# ethernet_dip_v1.net
KiCad netlist of a schematic drawn in EAGLE
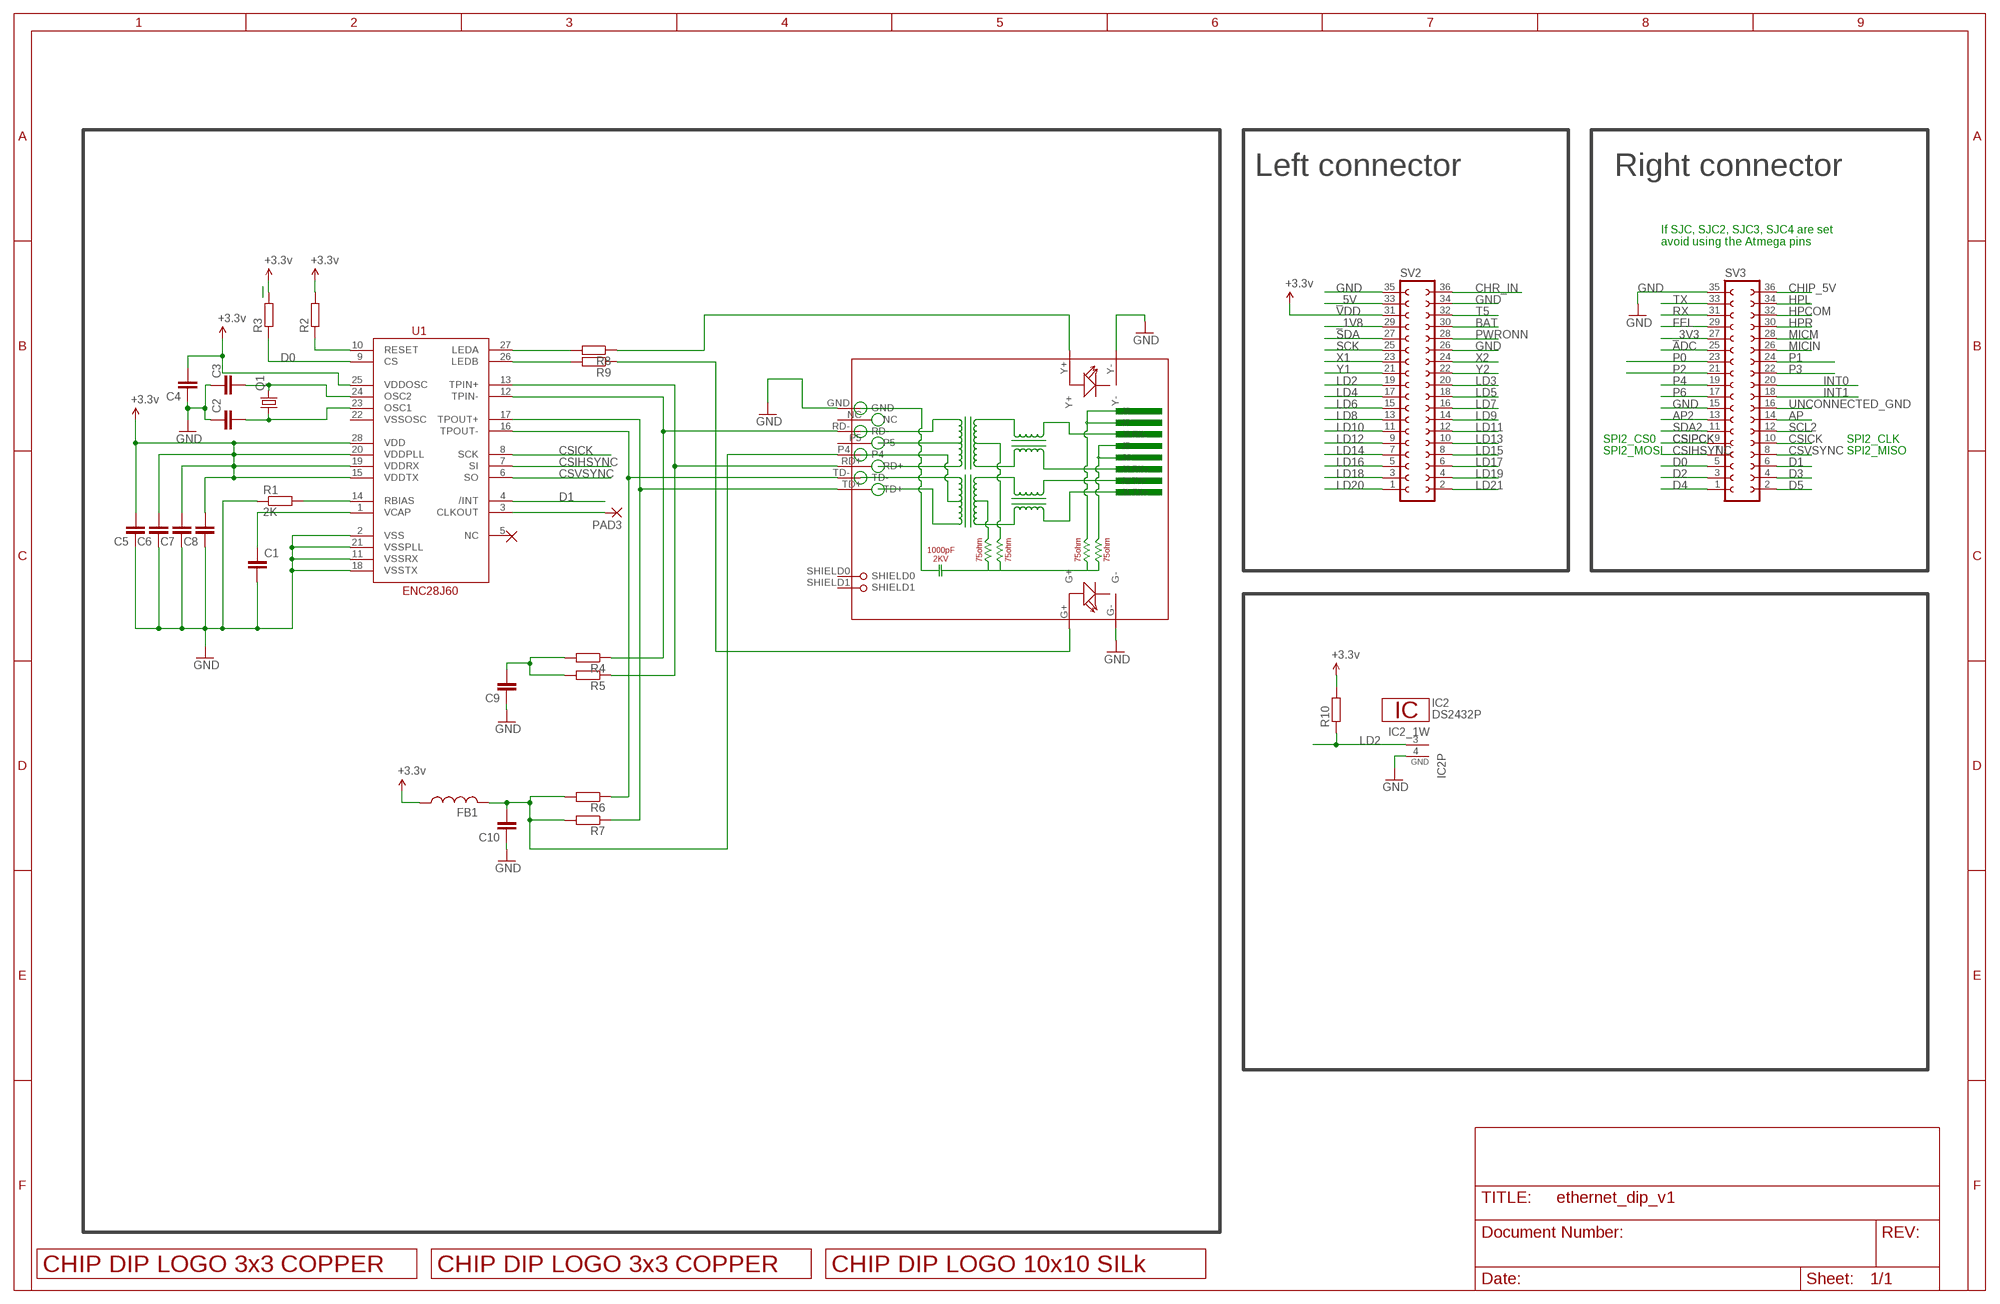
[diagram p0: schematic, sheet 1]

(export (version "E")
  (design (tool "Eeschema 10.0.6"))
  (components
    (comp (ref "C1")
      (value "C-EUC0805")
      (footprint "eagle-import:C0805")
      (libsource (lib "eagle-import") (part "C-EUC0805"))
    )
    (comp (ref "C2")
      (value "C-EUC0805")
      (footprint "eagle-import:C0805")
      (libsource (lib "eagle-import") (part "C-EUC0805"))
    )
    (comp (ref "C3")
      (value "C-EUC0805")
      (footprint "eagle-import:C0805")
      (libsource (lib "eagle-import") (part "C-EUC0805"))
    )
    (comp (ref "C4")
      (value "C-EUC0805")
      (footprint "eagle-import:C0805")
      (libsource (lib "eagle-import") (part "C-EUC0805"))
    )
    (comp (ref "C5")
      (value "C-EUC0805")
      (footprint "eagle-import:C0805")
      (libsource (lib "eagle-import") (part "C-EUC0805"))
    )
    (comp (ref "C6")
      (value "C-EUC0805")
      (footprint "eagle-import:C0805")
      (libsource (lib "eagle-import") (part "C-EUC0805"))
    )
    (comp (ref "C7")
      (value "C-EUC0805")
      (footprint "eagle-import:C0805")
      (libsource (lib "eagle-import") (part "C-EUC0805"))
    )
    (comp (ref "C8")
      (value "C-EUC0805")
      (footprint "eagle-import:C0805")
      (libsource (lib "eagle-import") (part "C-EUC0805"))
    )
    (comp (ref "C9")
      (value "C-EUC0805")
      (footprint "eagle-import:C0805")
      (libsource (lib "eagle-import") (part "C-EUC0805"))
    )
    (comp (ref "C10")
      (value "C-EUC0805")
      (footprint "eagle-import:C0805")
      (libsource (lib "eagle-import") (part "C-EUC0805"))
    )
    (comp (ref "FB1")
      (value "FERRITE-BEADB")
      (footprint "eagle-import:0805")
      (libsource (lib "eagle-import") (part "FERRITE-BEADB"))
    )
    (comp (ref "IC2")
      (value "DS2432P")
      (footprint "eagle-import:TSOC6")
      (libsource (lib "eagle-import") (part "DS2432P"))
    )
    (comp (ref "PAD3")
      (value "WIREPADSMD1,27-254")
      (footprint "eagle-import:SMD1,27-2,54")
      (libsource (lib "eagle-import") (part "WIREPADSMD1,27-254"))
    )
    (comp (ref "Q1")
      (value "CRYSTALSM49")
      (footprint "eagle-import:SM49")
      (libsource (lib "eagle-import") (part "CRYSTALSM49"))
    )
    (comp (ref "R1")
      (value "2K")
      (footprint "eagle-import:R0805")
      (libsource (lib "eagle-import") (part "R-EU_R0805"))
    )
    (comp (ref "R2")
      (value "R-EU_R0805")
      (footprint "eagle-import:R0805")
      (libsource (lib "eagle-import") (part "R-EU_R0805"))
    )
    (comp (ref "R3")
      (value "R-EU_R0805")
      (footprint "eagle-import:R0805")
      (libsource (lib "eagle-import") (part "R-EU_R0805"))
    )
    (comp (ref "R4")
      (value "R-EU_R0805")
      (footprint "eagle-import:R0805")
      (libsource (lib "eagle-import") (part "R-EU_R0805"))
    )
    (comp (ref "R5")
      (value "R-EU_R0805")
      (footprint "eagle-import:R0805")
      (libsource (lib "eagle-import") (part "R-EU_R0805"))
    )
    (comp (ref "R6")
      (value "R-EU_R0805")
      (footprint "eagle-import:R0805")
      (libsource (lib "eagle-import") (part "R-EU_R0805"))
    )
    (comp (ref "R7")
      (value "R-EU_R0805")
      (footprint "eagle-import:R0805")
      (libsource (lib "eagle-import") (part "R-EU_R0805"))
    )
    (comp (ref "R8")
      (value "R-EU_R0805")
      (footprint "eagle-import:R0805")
      (libsource (lib "eagle-import") (part "R-EU_R0805"))
    )
    (comp (ref "R9")
      (value "R-EU_R0805")
      (footprint "eagle-import:R0805")
      (libsource (lib "eagle-import") (part "R-EU_R0805"))
    )
    (comp (ref "R10")
      (value "R-EU_R0805")
      (footprint "eagle-import:R0805")
      (libsource (lib "eagle-import") (part "R-EU_R0805"))
    )
    (comp (ref "RJ1")
      (value "HR911105A")
      (footprint "eagle-import:HR911105A")
      (libsource (lib "eagle-import") (part "HR911105A"))
    )
    (comp (ref "SV2")
      (value "FE18-2")
      (footprint "eagle-import:FE18-2")
      (libsource (lib "eagle-import") (part "FE18-2"))
    )
    (comp (ref "SV3")
      (value "FE18-2")
      (footprint "eagle-import:FE18-2")
      (libsource (lib "eagle-import") (part "FE18-2"))
    )
    (comp (ref "U$2")
      (value "LOGO_3X3_COPPER")
      (footprint "eagle-import:LOGO_3X3_COPPER")
      (libsource (lib "eagle-import") (part "LOGO_3X3_COPPER"))
    )
    (comp (ref "U$4")
      (value "LOGO_3X3_COPPER")
      (footprint "eagle-import:LOGO_3X3_COPPER")
      (libsource (lib "eagle-import") (part "LOGO_3X3_COPPER"))
    )
    (comp (ref "U$5")
      (value "LOGO_10X10_SILK")
      (footprint "eagle-import:LOGO_10X10_SILK")
      (libsource (lib "eagle-import") (part "LOGO_10X10_SILK"))
    )
    (comp (ref "U1")
      (value "ENC28J60")
      (footprint "eagle-import:SSOP28DB")
      (libsource (lib "eagle-import") (part "ENC28J60"))
    )
  )
  (nets
    (net (code "1") (name "+3.3v") (class "Default")
      (node (ref "C4") (pin "2") (pinfunction "2_2") (pintype "passive"))
      (node (ref "C5") (pin "2") (pinfunction "2_2") (pintype "passive"))
      (node (ref "C6") (pin "2") (pinfunction "2_2") (pintype "passive"))
      (node (ref "C7") (pin "2") (pinfunction "2_2") (pintype "passive"))
      (node (ref "C8") (pin "2") (pinfunction "2_2") (pintype "passive"))
      (node (ref "FB1") (pin "1") (pinfunction "1_1") (pintype "passive"))
      (node (ref "R10") (pin "2") (pinfunction "2_2") (pintype "passive"))
      (node (ref "R2") (pin "2") (pinfunction "2_2") (pintype "passive"))
      (node (ref "R3") (pin "2") (pinfunction "2_2") (pintype "passive"))
      (node (ref "SV2") (pin "31") (pinfunction "31_31") (pintype "passive"))
      (node (ref "U1") (pin "15") (pinfunction "VDDTX_15") (pintype "bidirectional"))
      (node (ref "U1") (pin "19") (pinfunction "VDDRX_19") (pintype "bidirectional"))
      (node (ref "U1") (pin "20") (pinfunction "VDDPLL_20") (pintype "bidirectional"))
      (node (ref "U1") (pin "25") (pinfunction "VDDOSC_25") (pintype "bidirectional"))
      (node (ref "U1") (pin "28") (pinfunction "VDD_28") (pintype "bidirectional"))
    )
    (net (code "2") (name "/ADC") (class "Default")
      (node (ref "SV3") (pin "25") (pinfunction "25_25") (pintype "passive"))
    )
    (net (code "3") (name "/AP") (class "Default")
      (node (ref "SV3") (pin "14") (pinfunction "14_14") (pintype "passive"))
    )
    (net (code "4") (name "/AP2") (class "Default")
      (node (ref "SV3") (pin "13") (pinfunction "13_13") (pintype "passive"))
    )
    (net (code "5") (name "/BAT") (class "Default")
      (node (ref "SV2") (pin "30") (pinfunction "30_30") (pintype "passive"))
    )
    (net (code "6") (name "/CHIP_5V") (class "Default")
      (node (ref "SV3") (pin "36") (pinfunction "36_36") (pintype "passive"))
    )
    (net (code "7") (name "/CHR_IN") (class "Default")
      (node (ref "SV2") (pin "36") (pinfunction "36_36") (pintype "passive"))
    )
    (net (code "8") (name "/CSICK") (class "Default")
      (node (ref "SV3") (pin "10") (pinfunction "10_10") (pintype "passive"))
      (node (ref "U1") (pin "8") (pinfunction "SCK_8") (pintype "bidirectional"))
    )
    (net (code "9") (name "/CSIHSYNC") (class "Default")
      (node (ref "SV3") (pin "7") (pinfunction "7_7") (pintype "passive"))
      (node (ref "U1") (pin "7") (pinfunction "SI_7") (pintype "bidirectional"))
    )
    (net (code "10") (name "/CSIPCK") (class "Default")
      (node (ref "SV3") (pin "9") (pinfunction "9_9") (pintype "passive"))
    )
    (net (code "11") (name "/CSVSYNC") (class "Default")
      (node (ref "SV3") (pin "8") (pinfunction "8_8") (pintype "passive"))
      (node (ref "U1") (pin "6") (pinfunction "SO_6") (pintype "bidirectional"))
    )
    (net (code "12") (name "/D0") (class "Default")
      (node (ref "R3") (pin "1") (pinfunction "1_1") (pintype "passive"))
      (node (ref "SV3") (pin "5") (pinfunction "5_5") (pintype "passive"))
      (node (ref "U1") (pin "9") (pinfunction "CS_9") (pintype "bidirectional"))
    )
    (net (code "13") (name "/D1") (class "Default")
      (node (ref "SV3") (pin "6") (pinfunction "6_6") (pintype "passive"))
      (node (ref "U1") (pin "4") (pinfunction "/INT_4") (pintype "bidirectional"))
    )
    (net (code "14") (name "/D2") (class "Default")
      (node (ref "SV3") (pin "3") (pinfunction "3_3") (pintype "passive"))
    )
    (net (code "15") (name "/D3") (class "Default")
      (node (ref "SV3") (pin "4") (pinfunction "4_4") (pintype "passive"))
    )
    (net (code "16") (name "/D4") (class "Default")
      (node (ref "SV3") (pin "1") (pinfunction "1_1") (pintype "passive"))
    )
    (net (code "17") (name "/D5") (class "Default")
      (node (ref "SV3") (pin "2") (pinfunction "2_2") (pintype "passive"))
    )
    (net (code "18") (name "/FEL") (class "Default")
      (node (ref "SV3") (pin "29") (pinfunction "29_29") (pintype "passive"))
    )
    (net (code "19") (name "/HPCOM") (class "Default")
      (node (ref "SV3") (pin "32") (pinfunction "32_32") (pintype "passive"))
    )
    (net (code "20") (name "/HPL") (class "Default")
      (node (ref "SV3") (pin "34") (pinfunction "34_34") (pintype "passive"))
    )
    (net (code "21") (name "/HPR") (class "Default")
      (node (ref "SV3") (pin "30") (pinfunction "30_30") (pintype "passive"))
    )
    (net (code "22") (name "/INT0") (class "Default")
      (node (ref "SV3") (pin "20") (pinfunction "20_20") (pintype "passive"))
    )
    (net (code "23") (name "/INT1") (class "Default")
      (node (ref "SV3") (pin "18") (pinfunction "18_18") (pintype "passive"))
    )
    (net (code "24") (name "/LD2") (class "Default")
      (node (ref "IC2") (pin "3") (pinfunction "1W_3") (pintype "power_in"))
      (node (ref "R10") (pin "1") (pinfunction "1_1") (pintype "passive"))
      (node (ref "SV2") (pin "19") (pinfunction "19_19") (pintype "passive"))
    )
    (net (code "25") (name "/LD3") (class "Default")
      (node (ref "SV2") (pin "20") (pinfunction "20_20") (pintype "passive"))
    )
    (net (code "26") (name "/LD4") (class "Default")
      (node (ref "SV2") (pin "17") (pinfunction "17_17") (pintype "passive"))
    )
    (net (code "27") (name "/LD5") (class "Default")
      (node (ref "SV2") (pin "18") (pinfunction "18_18") (pintype "passive"))
    )
    (net (code "28") (name "/LD6") (class "Default")
      (node (ref "SV2") (pin "15") (pinfunction "15_15") (pintype "passive"))
    )
    (net (code "29") (name "/LD7") (class "Default")
      (node (ref "SV2") (pin "16") (pinfunction "16_16") (pintype "passive"))
    )
    (net (code "30") (name "/LD8") (class "Default")
      (node (ref "SV2") (pin "13") (pinfunction "13_13") (pintype "passive"))
    )
    (net (code "31") (name "/LD9") (class "Default")
      (node (ref "SV2") (pin "14") (pinfunction "14_14") (pintype "passive"))
    )
    (net (code "32") (name "/LD10") (class "Default")
      (node (ref "SV2") (pin "11") (pinfunction "11_11") (pintype "passive"))
    )
    (net (code "33") (name "/LD11") (class "Default")
      (node (ref "SV2") (pin "12") (pinfunction "12_12") (pintype "passive"))
    )
    (net (code "34") (name "/LD12") (class "Default")
      (node (ref "SV2") (pin "9") (pinfunction "9_9") (pintype "passive"))
    )
    (net (code "35") (name "/LD13") (class "Default")
      (node (ref "SV2") (pin "10") (pinfunction "10_10") (pintype "passive"))
    )
    (net (code "36") (name "/LD14") (class "Default")
      (node (ref "SV2") (pin "7") (pinfunction "7_7") (pintype "passive"))
    )
    (net (code "37") (name "/LD15") (class "Default")
      (node (ref "SV2") (pin "8") (pinfunction "8_8") (pintype "passive"))
    )
    (net (code "38") (name "/LD16") (class "Default")
      (node (ref "SV2") (pin "5") (pinfunction "5_5") (pintype "passive"))
    )
    (net (code "39") (name "/LD17") (class "Default")
      (node (ref "SV2") (pin "6") (pinfunction "6_6") (pintype "passive"))
    )
    (net (code "40") (name "/LD18") (class "Default")
      (node (ref "SV2") (pin "3") (pinfunction "3_3") (pintype "passive"))
    )
    (net (code "41") (name "/LD19") (class "Default")
      (node (ref "SV2") (pin "4") (pinfunction "4_4") (pintype "passive"))
    )
    (net (code "42") (name "/LD20") (class "Default")
      (node (ref "SV2") (pin "1") (pinfunction "1_1") (pintype "passive"))
    )
    (net (code "43") (name "/LD21") (class "Default")
      (node (ref "SV2") (pin "2") (pinfunction "2_2") (pintype "passive"))
    )
    (net (code "44") (name "/MICIN") (class "Default")
      (node (ref "SV3") (pin "26") (pinfunction "26_26") (pintype "passive"))
    )
    (net (code "45") (name "/MICM") (class "Default")
      (node (ref "SV3") (pin "28") (pinfunction "28_28") (pintype "passive"))
    )
    (net (code "46") (name "/P0") (class "Default")
      (node (ref "SV3") (pin "23") (pinfunction "23_23") (pintype "passive"))
    )
    (net (code "47") (name "/P1") (class "Default")
      (node (ref "SV3") (pin "24") (pinfunction "24_24") (pintype "passive"))
    )
    (net (code "48") (name "/P2") (class "Default")
      (node (ref "SV3") (pin "21") (pinfunction "21_21") (pintype "passive"))
    )
    (net (code "49") (name "/P3") (class "Default")
      (node (ref "SV3") (pin "22") (pinfunction "22_22") (pintype "passive"))
    )
    (net (code "50") (name "/P4") (class "Default")
      (node (ref "SV3") (pin "19") (pinfunction "19_19") (pintype "passive"))
    )
    (net (code "51") (name "/P6") (class "Default")
      (node (ref "SV3") (pin "17") (pinfunction "17_17") (pintype "passive"))
    )
    (net (code "52") (name "/PWRONN") (class "Default")
      (node (ref "SV2") (pin "28") (pinfunction "28_28") (pintype "passive"))
    )
    (net (code "53") (name "/RX") (class "Default")
      (node (ref "SV3") (pin "31") (pinfunction "31_31") (pintype "passive"))
    )
    (net (code "54") (name "/SCK") (class "Default")
      (node (ref "SV2") (pin "25") (pinfunction "25_25") (pintype "passive"))
    )
    (net (code "55") (name "/SCL2") (class "Default")
      (node (ref "SV3") (pin "12") (pinfunction "12_12") (pintype "passive"))
    )
    (net (code "56") (name "/SDA") (class "Default")
      (node (ref "SV2") (pin "27") (pinfunction "27_27") (pintype "passive"))
    )
    (net (code "57") (name "/SDA2") (class "Default")
      (node (ref "SV3") (pin "11") (pinfunction "11_11") (pintype "passive"))
    )
    (net (code "58") (name "/T5") (class "Default")
      (node (ref "SV2") (pin "32") (pinfunction "32_32") (pintype "passive"))
    )
    (net (code "59") (name "/TX") (class "Default")
      (node (ref "SV3") (pin "33") (pinfunction "33_33") (pintype "passive"))
    )
    (net (code "60") (name "/UNCONNECTED_GND") (class "Default")
      (node (ref "SV3") (pin "16") (pinfunction "16_16") (pintype "passive"))
    )
    (net (code "61") (name "/X1") (class "Default")
      (node (ref "SV2") (pin "23") (pinfunction "23_23") (pintype "passive"))
    )
    (net (code "62") (name "/X2") (class "Default")
      (node (ref "SV2") (pin "24") (pinfunction "24_24") (pintype "passive"))
    )
    (net (code "63") (name "/Y1") (class "Default")
      (node (ref "SV2") (pin "21") (pinfunction "21_21") (pintype "passive"))
    )
    (net (code "64") (name "/Y2") (class "Default")
      (node (ref "SV2") (pin "22") (pinfunction "22_22") (pintype "passive"))
    )
    (net (code "65") (name "/_1V8") (class "Default")
      (node (ref "SV2") (pin "29") (pinfunction "29_29") (pintype "passive"))
    )
    (net (code "66") (name "/_3V3") (class "Default")
      (node (ref "SV3") (pin "27") (pinfunction "27_27") (pintype "passive"))
    )
    (net (code "67") (name "/_5V") (class "Default")
      (node (ref "SV2") (pin "33") (pinfunction "33_33") (pintype "passive"))
    )
    (net (code "68") (name "GND") (class "Default")
      (node (ref "C1") (pin "2") (pinfunction "2_2") (pintype "passive"))
      (node (ref "C10") (pin "1") (pinfunction "1_1") (pintype "passive"))
      (node (ref "C2") (pin "1") (pinfunction "1_1") (pintype "passive"))
      (node (ref "C3") (pin "1") (pinfunction "1_1") (pintype "passive"))
      (node (ref "C4") (pin "1") (pinfunction "1_1") (pintype "passive"))
      (node (ref "C5") (pin "1") (pinfunction "1_1") (pintype "passive"))
      (node (ref "C6") (pin "1") (pinfunction "1_1") (pintype "passive"))
      (node (ref "C7") (pin "1") (pinfunction "1_1") (pintype "passive"))
      (node (ref "C8") (pin "1") (pinfunction "1_1") (pintype "passive"))
      (node (ref "C9") (pin "1") (pinfunction "1_1") (pintype "passive"))
      (node (ref "IC2") (pin "4") (pinfunction "GND_4") (pintype "power_in"))
      (node (ref "R1") (pin "1") (pinfunction "1_1") (pintype "passive"))
      (node (ref "RJ1") (pin "G-") (pinfunction "G-_G-") (pintype "bidirectional"))
      (node (ref "RJ1") (pin "GND") (pinfunction "GND_GND") (pintype "bidirectional"))
      (node (ref "RJ1") (pin "Y-") (pinfunction "Y-_Y-") (pintype "bidirectional"))
      (node (ref "SV2") (pin "26") (pinfunction "26_26") (pintype "passive"))
      (node (ref "SV2") (pin "34") (pinfunction "34_34") (pintype "passive"))
      (node (ref "SV2") (pin "35") (pinfunction "35_35") (pintype "passive"))
      (node (ref "SV3") (pin "15") (pinfunction "15_15") (pintype "passive"))
      (node (ref "SV3") (pin "35") (pinfunction "35_35") (pintype "passive"))
      (node (ref "U1") (pin "11") (pinfunction "VSSRX_11") (pintype "bidirectional"))
      (node (ref "U1") (pin "18") (pinfunction "VSSTX_18") (pintype "bidirectional"))
      (node (ref "U1") (pin "2") (pinfunction "VSS_2") (pintype "bidirectional"))
      (node (ref "U1") (pin "21") (pinfunction "VSSPLL_21") (pintype "bidirectional"))
    )
    (net (code "69") (name "Net-(C9-Pad2)") (class "Default")
      (node (ref "C9") (pin "2") (pinfunction "2_2") (pintype "passive"))
      (node (ref "R4") (pin "2") (pinfunction "2_2") (pintype "passive"))
      (node (ref "R5") (pin "2") (pinfunction "2_2") (pintype "passive"))
    )
    (net (code "70") (name "Net-(C10-Pad2)") (class "Default")
      (node (ref "C10") (pin "2") (pinfunction "2_2") (pintype "passive"))
      (node (ref "FB1") (pin "2") (pinfunction "2_2") (pintype "passive"))
      (node (ref "R6") (pin "2") (pinfunction "2_2") (pintype "passive"))
      (node (ref "R7") (pin "2") (pinfunction "2_2") (pintype "passive"))
      (node (ref "RJ1") (pin "P4") (pinfunction "P4_P4") (pintype "bidirectional"))
    )
    (net (code "71") (name "Net-(PAD3-P)") (class "Default")
      (node (ref "PAD3") (pin "1") (pinfunction "P_1") (pintype "passive"))
      (node (ref "U1") (pin "3") (pinfunction "CLKOUT_3") (pintype "bidirectional"))
    )
    (net (code "72") (name "Net-(R8-Pad1)") (class "Default")
      (node (ref "R8") (pin "1") (pinfunction "1_1") (pintype "passive"))
      (node (ref "RJ1") (pin "Y+") (pinfunction "Y+_Y+") (pintype "bidirectional"))
    )
    (net (code "73") (name "Net-(R9-Pad1)") (class "Default")
      (node (ref "R9") (pin "1") (pinfunction "1_1") (pintype "passive"))
      (node (ref "RJ1") (pin "G+") (pinfunction "G+_G+") (pintype "bidirectional"))
    )
    (net (code "74") (name "Net-(U1-LEDA)") (class "Default")
      (node (ref "R8") (pin "2") (pinfunction "2_2") (pintype "passive"))
      (node (ref "U1") (pin "27") (pinfunction "LEDA_27") (pintype "bidirectional"))
    )
    (net (code "75") (name "Net-(U1-LEDB)") (class "Default")
      (node (ref "R9") (pin "2") (pinfunction "2_2") (pintype "passive"))
      (node (ref "U1") (pin "26") (pinfunction "LEDB_26") (pintype "bidirectional"))
    )
    (net (code "76") (name "Net-(U1-OSC1)") (class "Default")
      (node (ref "C2") (pin "2") (pinfunction "2_2") (pintype "passive"))
      (node (ref "Q1") (pin "1") (pinfunction "1_1") (pintype "passive"))
      (node (ref "U1") (pin "23") (pinfunction "OSC1_23") (pintype "bidirectional"))
    )
    (net (code "77") (name "Net-(U1-OSC2)") (class "Default")
      (node (ref "C3") (pin "2") (pinfunction "2_2") (pintype "passive"))
      (node (ref "Q1") (pin "2") (pinfunction "2_2") (pintype "passive"))
      (node (ref "U1") (pin "24") (pinfunction "OSC2_24") (pintype "bidirectional"))
    )
    (net (code "78") (name "Net-(U1-RBIAS)") (class "Default")
      (node (ref "R1") (pin "2") (pinfunction "2_2") (pintype "passive"))
      (node (ref "U1") (pin "14") (pinfunction "RBIAS_14") (pintype "bidirectional"))
    )
    (net (code "79") (name "Net-(U1-RESET)") (class "Default")
      (node (ref "R2") (pin "1") (pinfunction "1_1") (pintype "passive"))
      (node (ref "U1") (pin "10") (pinfunction "RESET_10") (pintype "bidirectional"))
    )
    (net (code "80") (name "Net-(U1-TPIN+)") (class "Default")
      (node (ref "R5") (pin "1") (pinfunction "1_1") (pintype "passive"))
      (node (ref "RJ1") (pin "RD+") (pinfunction "RD+_RD+") (pintype "bidirectional"))
      (node (ref "U1") (pin "13") (pinfunction "TPIN+_13") (pintype "bidirectional"))
    )
    (net (code "81") (name "Net-(U1-TPIN-)") (class "Default")
      (node (ref "R4") (pin "1") (pinfunction "1_1") (pintype "passive"))
      (node (ref "RJ1") (pin "RD-") (pinfunction "RD-_RD-") (pintype "bidirectional"))
      (node (ref "U1") (pin "12") (pinfunction "TPIN-_12") (pintype "bidirectional"))
    )
    (net (code "82") (name "Net-(U1-TPOUT+)") (class "Default")
      (node (ref "R7") (pin "1") (pinfunction "1_1") (pintype "passive"))
      (node (ref "RJ1") (pin "TD+") (pinfunction "TD+_TD+") (pintype "bidirectional"))
      (node (ref "U1") (pin "17") (pinfunction "TPOUT+_17") (pintype "bidirectional"))
    )
    (net (code "83") (name "Net-(U1-TPOUT-)") (class "Default")
      (node (ref "R6") (pin "1") (pinfunction "1_1") (pintype "passive"))
      (node (ref "RJ1") (pin "TD-") (pinfunction "TD-_TD-") (pintype "bidirectional"))
      (node (ref "U1") (pin "16") (pinfunction "TPOUT-_16") (pintype "bidirectional"))
    )
    (net (code "84") (name "Net-(U1-VCAP)") (class "Default")
      (node (ref "C1") (pin "1") (pinfunction "1_1") (pintype "passive"))
      (node (ref "U1") (pin "1") (pinfunction "VCAP_1") (pintype "bidirectional"))
    )
    (net (code "85") (name "unconnected-(RJ1-PadNC)") (class "Default")
      (node (ref "RJ1") (pin "NC") (pinfunction "NC_NC") (pintype "bidirectional"))
    )
    (net (code "86") (name "unconnected-(RJ1-PadP5)") (class "Default")
      (node (ref "RJ1") (pin "P5") (pinfunction "P5_P5") (pintype "bidirectional"))
    )
    (net (code "87") (name "unconnected-(RJ1-PadSHIELD0)") (class "Default")
      (node (ref "RJ1") (pin "SHIELD0") (pinfunction "SHIELD0_SHIELD0") (pintype "bidirectional"))
    )
    (net (code "88") (name "unconnected-(RJ1-PadSHIELD1)") (class "Default")
      (node (ref "RJ1") (pin "SHIELD1") (pinfunction "SHIELD1_SHIELD1") (pintype "bidirectional"))
    )
    (net (code "89") (name "unconnected-(U1-NC-Pad5)") (class "Default")
      (node (ref "U1") (pin "5") (pinfunction "NC_5") (pintype "bidirectional"))
    )
    (net (code "90") (name "unconnected-(U1-VSSOSC-Pad22)") (class "Default")
      (node (ref "U1") (pin "22") (pinfunction "VSSOSC_22") (pintype "bidirectional"))
    )
  )
)
